# FT232H.net
KiCad netlist of a schematic drawn in EAGLE
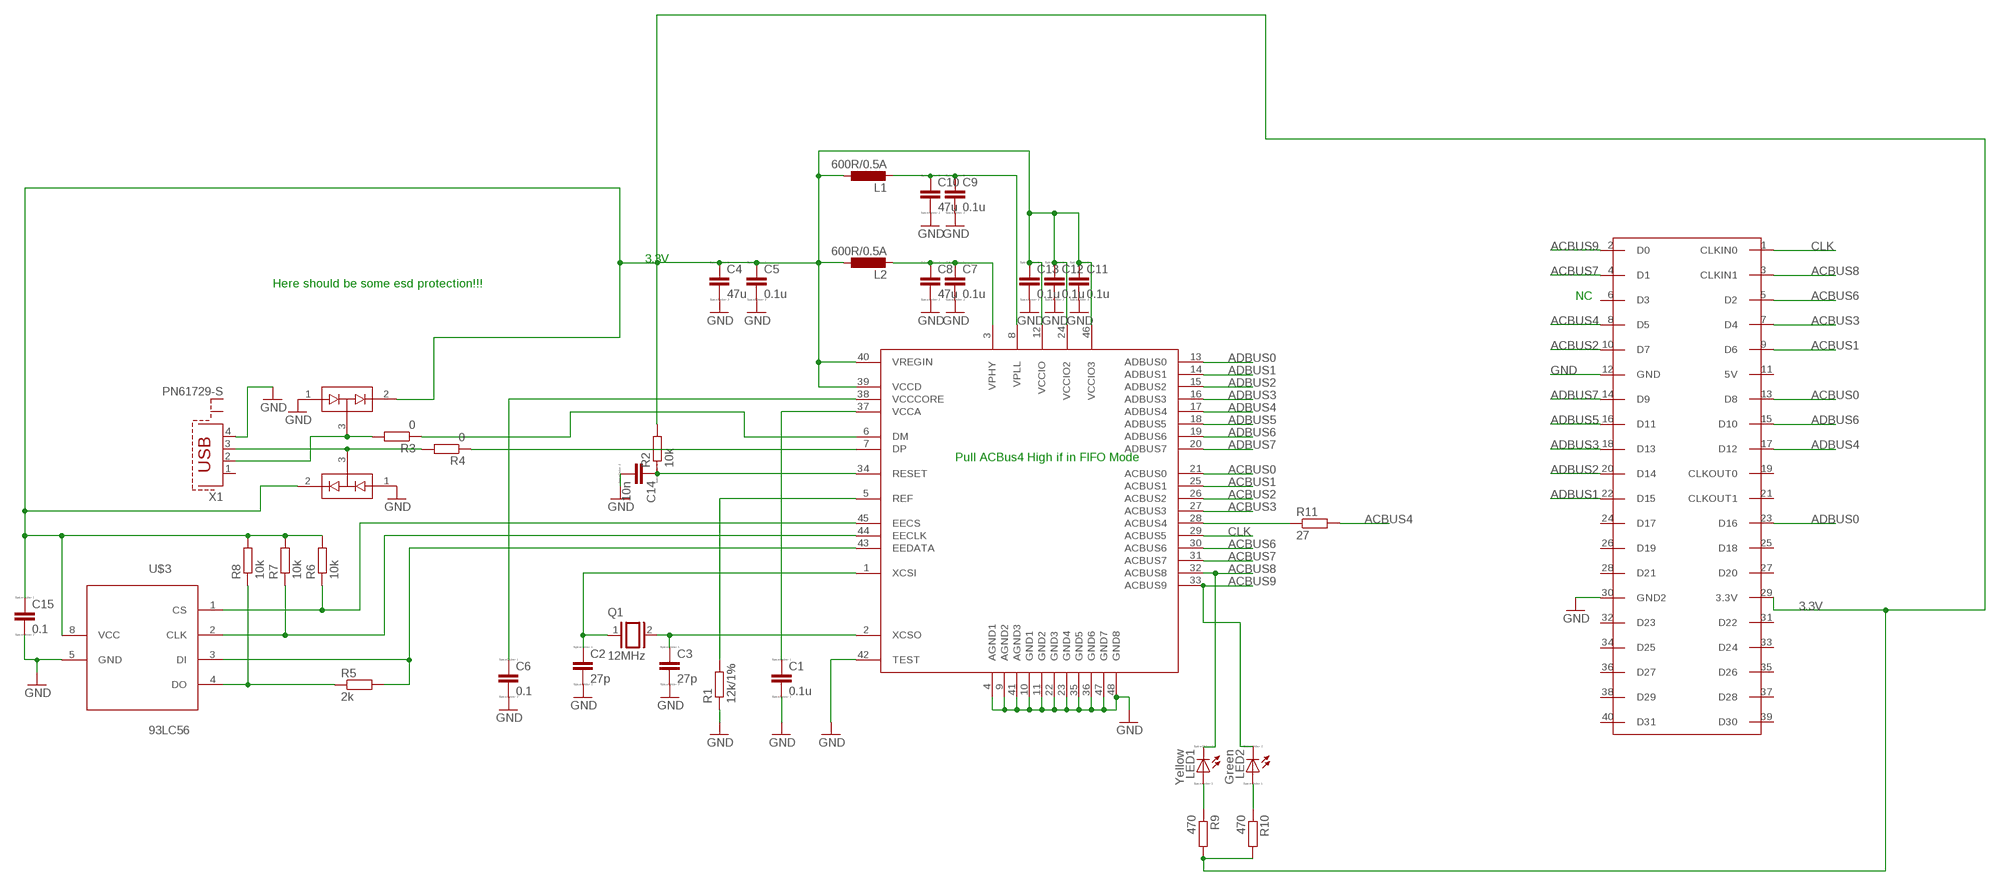
[diagram p0: schematic, sheet 1]

(export (version "E")
  (design (tool "Eeschema 10.0.6"))
  (components
    (comp (ref "C1")
      (value "0.1u")
      (footprint "eagle-import:C0805")
      (libsource (lib "eagle-import") (part "C_SMD"))
    )
    (comp (ref "C2")
      (value "27p")
      (footprint "eagle-import:C0805")
      (libsource (lib "eagle-import") (part "C_SMD"))
    )
    (comp (ref "C3")
      (value "27p")
      (footprint "eagle-import:C0805")
      (libsource (lib "eagle-import") (part "C_SMD"))
    )
    (comp (ref "C4")
      (value "47u")
      (footprint "eagle-import:C0805")
      (libsource (lib "eagle-import") (part "C_SMD"))
    )
    (comp (ref "C5")
      (value "0.1u")
      (footprint "eagle-import:C0805")
      (libsource (lib "eagle-import") (part "C_SMD"))
    )
    (comp (ref "C6")
      (value "0.1")
      (footprint "eagle-import:C0805")
      (libsource (lib "eagle-import") (part "C_SMD"))
    )
    (comp (ref "C7")
      (value "0.1u")
      (footprint "eagle-import:C0805")
      (libsource (lib "eagle-import") (part "C_SMD"))
    )
    (comp (ref "C8")
      (value "47u")
      (footprint "eagle-import:C0805")
      (libsource (lib "eagle-import") (part "C_SMD"))
    )
    (comp (ref "C9")
      (value "0.1u")
      (footprint "eagle-import:C0805")
      (libsource (lib "eagle-import") (part "C_SMD"))
    )
    (comp (ref "C10")
      (value "47u")
      (footprint "eagle-import:C0805")
      (libsource (lib "eagle-import") (part "C_SMD"))
    )
    (comp (ref "C11")
      (value "0.1u")
      (footprint "eagle-import:C0805")
      (libsource (lib "eagle-import") (part "C_SMD"))
    )
    (comp (ref "C12")
      (value "0.1u")
      (footprint "eagle-import:C0805")
      (libsource (lib "eagle-import") (part "C_SMD"))
    )
    (comp (ref "C13")
      (value "0.1u")
      (footprint "eagle-import:C0805")
      (libsource (lib "eagle-import") (part "C_SMD"))
    )
    (comp (ref "C14")
      (value "10n")
      (footprint "eagle-import:C0805")
      (libsource (lib "eagle-import") (part "C_SMD"))
    )
    (comp (ref "C15")
      (value "0.1")
      (footprint "eagle-import:C0805")
      (libsource (lib "eagle-import") (part "C_SMD"))
    )
    (comp (ref "D1")
      (value "BAV99")
      (footprint "eagle-import:SOT23")
      (libsource (lib "eagle-import") (part "BAV99"))
    )
    (comp (ref "D2")
      (value "BAV99")
      (footprint "eagle-import:SOT23")
      (libsource (lib "eagle-import") (part "BAV99"))
    )
    (comp (ref "L1")
      (value "600R/0.5A")
      (footprint "eagle-import:R0805")
      (libsource (lib "eagle-import") (part "L_0805"))
    )
    (comp (ref "L2")
      (value "600R/0.5A")
      (footprint "eagle-import:R0805")
      (libsource (lib "eagle-import") (part "L_0805"))
    )
    (comp (ref "LED1")
      (value "Yellow")
      (footprint "eagle-import:R0805")
      (libsource (lib "eagle-import") (part "LED_ELED_0805"))
    )
    (comp (ref "LED2")
      (value "Green")
      (footprint "eagle-import:R0805")
      (libsource (lib "eagle-import") (part "LED_ELED_0805"))
    )
    (comp (ref "Q1")
      (value "12MHz")
      (footprint "eagle-import:QS")
      (libsource (lib "eagle-import") (part "XTAL/S"))
    )
    (comp (ref "R1")
      (value "12k/1%")
      (footprint "eagle-import:M0805")
      (libsource (lib "eagle-import") (part "R-EU_M0805"))
    )
    (comp (ref "R2")
      (value "10k")
      (footprint "eagle-import:M0805")
      (libsource (lib "eagle-import") (part "R-EU_M0805"))
    )
    (comp (ref "R3")
      (value "0")
      (footprint "eagle-import:M0805")
      (libsource (lib "eagle-import") (part "R-EU_M0805"))
    )
    (comp (ref "R4")
      (value "0")
      (footprint "eagle-import:M0805")
      (libsource (lib "eagle-import") (part "R-EU_M0805"))
    )
    (comp (ref "R5")
      (value "2k")
      (footprint "eagle-import:M0805")
      (libsource (lib "eagle-import") (part "R-EU_M0805"))
    )
    (comp (ref "R6")
      (value "10k")
      (footprint "eagle-import:M0805")
      (libsource (lib "eagle-import") (part "R-EU_M0805"))
    )
    (comp (ref "R7")
      (value "10k")
      (footprint "eagle-import:M0805")
      (libsource (lib "eagle-import") (part "R-EU_M0805"))
    )
    (comp (ref "R8")
      (value "10k")
      (footprint "eagle-import:M0805")
      (libsource (lib "eagle-import") (part "R-EU_M0805"))
    )
    (comp (ref "R9")
      (value "470")
      (footprint "eagle-import:M0805")
      (libsource (lib "eagle-import") (part "R-EU_M0805"))
    )
    (comp (ref "R10")
      (value "470")
      (footprint "eagle-import:M0805")
      (libsource (lib "eagle-import") (part "R-EU_M0805"))
    )
    (comp (ref "R11")
      (value "27")
      (footprint "eagle-import:M0805")
      (libsource (lib "eagle-import") (part "R-EU_M0805"))
    )
    (comp (ref "U$1")
      (value "FT232H")
      (footprint "eagle-import:LQFP48")
      (libsource (lib "eagle-import") (part "FT232H"))
    )
    (comp (ref "U$2")
      (value "FPGA_GPIO_DE0")
      (footprint "eagle-import:2X20")
      (libsource (lib "eagle-import") (part "FPGA_GPIO_DE0"))
    )
    (comp (ref "U$3")
      (value "93LC56")
      (footprint "eagle-import:DIL-08")
      (libsource (lib "eagle-import") (part "93LC56"))
    )
    (comp (ref "X1")
      (value "PN61729-S")
      (footprint "eagle-import:PN61729-S")
      (libsource (lib "eagle-import") (part "PN61729-S"))
    )
  )
  (nets
    (net (code "1") (name "/3.3V") (class "Default")
      (node (ref "C11") (pin "1") (pinfunction "1_1") (pintype "passive"))
      (node (ref "C12") (pin "1") (pinfunction "1_1") (pintype "passive"))
      (node (ref "C13") (pin "1") (pinfunction "1_1") (pintype "passive"))
      (node (ref "C15") (pin "1") (pinfunction "1_1") (pintype "passive"))
      (node (ref "C4") (pin "1") (pinfunction "1_1") (pintype "passive"))
      (node (ref "C5") (pin "1") (pinfunction "1_1") (pintype "passive"))
      (node (ref "D1") (pin "2") (pinfunction "C2_2") (pintype "bidirectional"))
      (node (ref "D2") (pin "2") (pinfunction "C2_2") (pintype "bidirectional"))
      (node (ref "L1") (pin "1") (pinfunction "1_1") (pintype "passive"))
      (node (ref "L2") (pin "1") (pinfunction "1_1") (pintype "passive"))
      (node (ref "R10") (pin "2") (pinfunction "2_2") (pintype "passive"))
      (node (ref "R2") (pin "2") (pinfunction "2_2") (pintype "passive"))
      (node (ref "R6") (pin "2") (pinfunction "2_2") (pintype "passive"))
      (node (ref "R7") (pin "2") (pinfunction "2_2") (pintype "passive"))
      (node (ref "R8") (pin "2") (pinfunction "2_2") (pintype "passive"))
      (node (ref "R9") (pin "2") (pinfunction "2_2") (pintype "passive"))
      (node (ref "U$1") (pin "12") (pinfunction "VCCIO_12") (pintype "bidirectional"))
      (node (ref "U$1") (pin "24") (pinfunction "VCCIO2_24") (pintype "bidirectional"))
      (node (ref "U$1") (pin "39") (pinfunction "VCCD_39") (pintype "bidirectional"))
      (node (ref "U$1") (pin "40") (pinfunction "VREGIN_40") (pintype "bidirectional"))
      (node (ref "U$1") (pin "46") (pinfunction "VCCIO3_46") (pintype "bidirectional"))
      (node (ref "U$2") (pin "29") (pinfunction "3.3V_29") (pintype "bidirectional"))
      (node (ref "U$3") (pin "8") (pinfunction "VCC_8") (pintype "bidirectional"))
    )
    (net (code "2") (name "/ACBUS0") (class "Default")
      (node (ref "U$1") (pin "21") (pinfunction "ACBUS0_21") (pintype "bidirectional"))
      (node (ref "U$2") (pin "13") (pinfunction "D8_13") (pintype "bidirectional"))
    )
    (net (code "3") (name "/ACBUS1") (class "Default")
      (node (ref "U$1") (pin "25") (pinfunction "ACBUS1_25") (pintype "bidirectional"))
      (node (ref "U$2") (pin "9") (pinfunction "D6_9") (pintype "bidirectional"))
    )
    (net (code "4") (name "/ACBUS2") (class "Default")
      (node (ref "U$1") (pin "26") (pinfunction "ACBUS2_26") (pintype "bidirectional"))
      (node (ref "U$2") (pin "10") (pinfunction "D7_10") (pintype "bidirectional"))
    )
    (net (code "5") (name "/ACBUS3") (class "Default")
      (node (ref "U$1") (pin "27") (pinfunction "ACBUS3_27") (pintype "bidirectional"))
      (node (ref "U$2") (pin "7") (pinfunction "D4_7") (pintype "bidirectional"))
    )
    (net (code "6") (name "/ACBUS4") (class "Default")
      (node (ref "R11") (pin "2") (pinfunction "2_2") (pintype "passive"))
      (node (ref "U$2") (pin "8") (pinfunction "D5_8") (pintype "bidirectional"))
    )
    (net (code "7") (name "/ACBUS6") (class "Default")
      (node (ref "U$1") (pin "30") (pinfunction "ACBUS6_30") (pintype "bidirectional"))
      (node (ref "U$2") (pin "5") (pinfunction "D2_5") (pintype "bidirectional"))
    )
    (net (code "8") (name "/ACBUS7") (class "Default")
      (node (ref "U$1") (pin "31") (pinfunction "ACBUS7_31") (pintype "bidirectional"))
      (node (ref "U$2") (pin "4") (pinfunction "D1_4") (pintype "bidirectional"))
    )
    (net (code "9") (name "/ACBUS8") (class "Default")
      (node (ref "LED1") (pin "2") (pinfunction "C_2") (pintype "passive"))
      (node (ref "U$1") (pin "32") (pinfunction "ACBUS8_32") (pintype "bidirectional"))
      (node (ref "U$2") (pin "3") (pinfunction "CLKIN1_3") (pintype "bidirectional"))
    )
    (net (code "10") (name "/ACBUS9") (class "Default")
      (node (ref "LED2") (pin "2") (pinfunction "C_2") (pintype "passive"))
      (node (ref "U$1") (pin "33") (pinfunction "ACBUS9_33") (pintype "bidirectional"))
      (node (ref "U$2") (pin "2") (pinfunction "D0_2") (pintype "bidirectional"))
    )
    (net (code "11") (name "/ADBUS0") (class "Default")
      (node (ref "U$1") (pin "13") (pinfunction "ADBUS0_13") (pintype "bidirectional"))
      (node (ref "U$2") (pin "23") (pinfunction "D16_23") (pintype "bidirectional"))
    )
    (net (code "12") (name "/ADBUS1") (class "Default")
      (node (ref "U$1") (pin "14") (pinfunction "ADBUS1_14") (pintype "bidirectional"))
      (node (ref "U$2") (pin "22") (pinfunction "D15_22") (pintype "bidirectional"))
    )
    (net (code "13") (name "/ADBUS2") (class "Default")
      (node (ref "U$1") (pin "15") (pinfunction "ADBUS2_15") (pintype "bidirectional"))
      (node (ref "U$2") (pin "20") (pinfunction "D14_20") (pintype "bidirectional"))
    )
    (net (code "14") (name "/ADBUS3") (class "Default")
      (node (ref "U$1") (pin "16") (pinfunction "ADBUS3_16") (pintype "bidirectional"))
      (node (ref "U$2") (pin "18") (pinfunction "D13_18") (pintype "bidirectional"))
    )
    (net (code "15") (name "/ADBUS4") (class "Default")
      (node (ref "U$1") (pin "17") (pinfunction "ADBUS4_17") (pintype "bidirectional"))
      (node (ref "U$2") (pin "17") (pinfunction "D12_17") (pintype "bidirectional"))
    )
    (net (code "16") (name "/ADBUS5") (class "Default")
      (node (ref "U$1") (pin "18") (pinfunction "ADBUS5_18") (pintype "bidirectional"))
      (node (ref "U$2") (pin "16") (pinfunction "D11_16") (pintype "bidirectional"))
    )
    (net (code "17") (name "/ADBUS6") (class "Default")
      (node (ref "U$1") (pin "19") (pinfunction "ADBUS6_19") (pintype "bidirectional"))
      (node (ref "U$2") (pin "15") (pinfunction "D10_15") (pintype "bidirectional"))
    )
    (net (code "18") (name "/ADBUS7") (class "Default")
      (node (ref "U$1") (pin "20") (pinfunction "ADBUS7_20") (pintype "bidirectional"))
      (node (ref "U$2") (pin "14") (pinfunction "D9_14") (pintype "bidirectional"))
    )
    (net (code "19") (name "/CLK") (class "Default")
      (node (ref "U$1") (pin "29") (pinfunction "ACBUS5_29") (pintype "bidirectional"))
      (node (ref "U$2") (pin "1") (pinfunction "CLKIN0_1") (pintype "bidirectional"))
    )
    (net (code "20") (name "GND") (class "Default")
      (node (ref "C1") (pin "2") (pinfunction "2_2") (pintype "passive"))
      (node (ref "C10") (pin "2") (pinfunction "2_2") (pintype "passive"))
      (node (ref "C11") (pin "2") (pinfunction "2_2") (pintype "passive"))
      (node (ref "C12") (pin "2") (pinfunction "2_2") (pintype "passive"))
      (node (ref "C13") (pin "2") (pinfunction "2_2") (pintype "passive"))
      (node (ref "C14") (pin "2") (pinfunction "2_2") (pintype "passive"))
      (node (ref "C15") (pin "2") (pinfunction "2_2") (pintype "passive"))
      (node (ref "C2") (pin "2") (pinfunction "2_2") (pintype "passive"))
      (node (ref "C3") (pin "2") (pinfunction "2_2") (pintype "passive"))
      (node (ref "C4") (pin "2") (pinfunction "2_2") (pintype "passive"))
      (node (ref "C5") (pin "2") (pinfunction "2_2") (pintype "passive"))
      (node (ref "C6") (pin "2") (pinfunction "2_2") (pintype "passive"))
      (node (ref "C7") (pin "2") (pinfunction "2_2") (pintype "passive"))
      (node (ref "C8") (pin "2") (pinfunction "2_2") (pintype "passive"))
      (node (ref "C9") (pin "2") (pinfunction "2_2") (pintype "passive"))
      (node (ref "D1") (pin "1") (pinfunction "A1_1") (pintype "bidirectional"))
      (node (ref "D2") (pin "1") (pinfunction "A1_1") (pintype "bidirectional"))
      (node (ref "R1") (pin "1") (pinfunction "1_1") (pintype "passive"))
      (node (ref "U$1") (pin "10") (pinfunction "GND1_10") (pintype "bidirectional"))
      (node (ref "U$1") (pin "11") (pinfunction "GND2_11") (pintype "bidirectional"))
      (node (ref "U$1") (pin "22") (pinfunction "GND3_22") (pintype "bidirectional"))
      (node (ref "U$1") (pin "23") (pinfunction "GND4_23") (pintype "bidirectional"))
      (node (ref "U$1") (pin "35") (pinfunction "GND5_35") (pintype "bidirectional"))
      (node (ref "U$1") (pin "36") (pinfunction "GND6_36") (pintype "bidirectional"))
      (node (ref "U$1") (pin "4") (pinfunction "AGND1_4") (pintype "bidirectional"))
      (node (ref "U$1") (pin "41") (pinfunction "AGND3_41") (pintype "bidirectional"))
      (node (ref "U$1") (pin "42") (pinfunction "TEST_42") (pintype "bidirectional"))
      (node (ref "U$1") (pin "47") (pinfunction "GND7_47") (pintype "bidirectional"))
      (node (ref "U$1") (pin "48") (pinfunction "GND8_48") (pintype "bidirectional"))
      (node (ref "U$1") (pin "9") (pinfunction "AGND2_9") (pintype "bidirectional"))
      (node (ref "U$2") (pin "12") (pinfunction "GND_12") (pintype "bidirectional"))
      (node (ref "U$2") (pin "30") (pinfunction "GND2_30") (pintype "bidirectional"))
      (node (ref "U$3") (pin "5") (pinfunction "GND_5") (pintype "bidirectional"))
      (node (ref "X1") (pin "4") (pinfunction "4_4") (pintype "passive"))
    )
    (net (code "21") (name "Net-(D1-COM)") (class "Default")
      (node (ref "D1") (pin "3") (pinfunction "COM_3") (pintype "bidirectional"))
      (node (ref "R3") (pin "2") (pinfunction "2_2") (pintype "passive"))
      (node (ref "X1") (pin "2") (pinfunction "2_2") (pintype "passive"))
    )
    (net (code "22") (name "Net-(D2-COM)") (class "Default")
      (node (ref "D2") (pin "3") (pinfunction "COM_3") (pintype "bidirectional"))
      (node (ref "R4") (pin "2") (pinfunction "2_2") (pintype "passive"))
      (node (ref "X1") (pin "3") (pinfunction "3_3") (pintype "passive"))
    )
    (net (code "23") (name "Net-(LED1-A)") (class "Default")
      (node (ref "LED1") (pin "1") (pinfunction "A_1") (pintype "passive"))
      (node (ref "R9") (pin "1") (pinfunction "1_1") (pintype "passive"))
    )
    (net (code "24") (name "Net-(LED2-A)") (class "Default")
      (node (ref "LED2") (pin "1") (pinfunction "A_1") (pintype "passive"))
      (node (ref "R10") (pin "1") (pinfunction "1_1") (pintype "passive"))
    )
    (net (code "25") (name "Net-(U$1-ACBUS4)") (class "Default")
      (node (ref "R11") (pin "1") (pinfunction "1_1") (pintype "passive"))
      (node (ref "U$1") (pin "28") (pinfunction "ACBUS4_28") (pintype "bidirectional"))
    )
    (net (code "26") (name "Net-(U$1-DM)") (class "Default")
      (node (ref "R3") (pin "1") (pinfunction "1_1") (pintype "passive"))
      (node (ref "U$1") (pin "6") (pinfunction "DM_6") (pintype "bidirectional"))
    )
    (net (code "27") (name "Net-(U$1-DP)") (class "Default")
      (node (ref "R4") (pin "1") (pinfunction "1_1") (pintype "passive"))
      (node (ref "U$1") (pin "7") (pinfunction "DP_7") (pintype "bidirectional"))
    )
    (net (code "28") (name "Net-(U$1-EECLK)") (class "Default")
      (node (ref "R7") (pin "1") (pinfunction "1_1") (pintype "passive"))
      (node (ref "U$1") (pin "44") (pinfunction "EECLK_44") (pintype "bidirectional"))
      (node (ref "U$3") (pin "2") (pinfunction "CLK_2") (pintype "bidirectional"))
    )
    (net (code "29") (name "Net-(U$1-EECS)") (class "Default")
      (node (ref "R6") (pin "1") (pinfunction "1_1") (pintype "passive"))
      (node (ref "U$1") (pin "45") (pinfunction "EECS_45") (pintype "bidirectional"))
      (node (ref "U$3") (pin "1") (pinfunction "CS_1") (pintype "bidirectional"))
    )
    (net (code "30") (name "Net-(U$1-EEDATA)") (class "Default")
      (node (ref "R5") (pin "2") (pinfunction "2_2") (pintype "passive"))
      (node (ref "U$1") (pin "43") (pinfunction "EEDATA_43") (pintype "bidirectional"))
      (node (ref "U$3") (pin "3") (pinfunction "DI_3") (pintype "bidirectional"))
    )
    (net (code "31") (name "Net-(U$1-REF)") (class "Default")
      (node (ref "R1") (pin "2") (pinfunction "2_2") (pintype "passive"))
      (node (ref "U$1") (pin "5") (pinfunction "REF_5") (pintype "bidirectional"))
    )
    (net (code "32") (name "Net-(U$1-RESET)") (class "Default")
      (node (ref "C14") (pin "1") (pinfunction "1_1") (pintype "passive"))
      (node (ref "R2") (pin "1") (pinfunction "1_1") (pintype "passive"))
      (node (ref "U$1") (pin "34") (pinfunction "RESET_34") (pintype "bidirectional"))
    )
    (net (code "33") (name "Net-(U$1-VCCA)") (class "Default")
      (node (ref "C1") (pin "1") (pinfunction "1_1") (pintype "passive"))
      (node (ref "U$1") (pin "37") (pinfunction "VCCA_37") (pintype "bidirectional"))
    )
    (net (code "34") (name "Net-(U$1-VCCCORE)") (class "Default")
      (node (ref "C6") (pin "1") (pinfunction "1_1") (pintype "passive"))
      (node (ref "U$1") (pin "38") (pinfunction "VCCCORE_38") (pintype "bidirectional"))
    )
    (net (code "35") (name "Net-(U$1-VPHY)") (class "Default")
      (node (ref "C7") (pin "1") (pinfunction "1_1") (pintype "passive"))
      (node (ref "C8") (pin "1") (pinfunction "1_1") (pintype "passive"))
      (node (ref "L2") (pin "2") (pinfunction "2_2") (pintype "passive"))
      (node (ref "U$1") (pin "3") (pinfunction "VPHY_3") (pintype "bidirectional"))
    )
    (net (code "36") (name "Net-(U$1-VPLL)") (class "Default")
      (node (ref "C10") (pin "1") (pinfunction "1_1") (pintype "passive"))
      (node (ref "C9") (pin "1") (pinfunction "1_1") (pintype "passive"))
      (node (ref "L1") (pin "2") (pinfunction "2_2") (pintype "passive"))
      (node (ref "U$1") (pin "8") (pinfunction "VPLL_8") (pintype "bidirectional"))
    )
    (net (code "37") (name "Net-(U$1-XCSI)") (class "Default")
      (node (ref "C2") (pin "1") (pinfunction "1_1") (pintype "passive"))
      (node (ref "Q1") (pin "1") (pinfunction "1_1") (pintype "passive"))
      (node (ref "U$1") (pin "1") (pinfunction "XCSI_1") (pintype "bidirectional"))
    )
    (net (code "38") (name "Net-(U$1-XCSO)") (class "Default")
      (node (ref "C3") (pin "1") (pinfunction "1_1") (pintype "passive"))
      (node (ref "Q1") (pin "2") (pinfunction "2_2") (pintype "passive"))
      (node (ref "U$1") (pin "2") (pinfunction "XCSO_2") (pintype "bidirectional"))
    )
    (net (code "39") (name "Net-(U$3-DO)") (class "Default")
      (node (ref "R5") (pin "1") (pinfunction "1_1") (pintype "passive"))
      (node (ref "R8") (pin "1") (pinfunction "1_1") (pintype "passive"))
      (node (ref "U$3") (pin "4") (pinfunction "DO_4") (pintype "bidirectional"))
    )
    (net (code "40") (name "unconnected-(U$2-5V-Pad11)") (class "Default")
      (node (ref "U$2") (pin "11") (pinfunction "5V_11") (pintype "bidirectional"))
    )
    (net (code "41") (name "unconnected-(U$2-CLKOUT0-Pad19)") (class "Default")
      (node (ref "U$2") (pin "19") (pinfunction "CLKOUT0_19") (pintype "bidirectional"))
    )
    (net (code "42") (name "unconnected-(U$2-CLKOUT1-Pad21)") (class "Default")
      (node (ref "U$2") (pin "21") (pinfunction "CLKOUT1_21") (pintype "bidirectional"))
    )
    (net (code "43") (name "unconnected-(U$2-D3-Pad6)") (class "Default")
      (node (ref "U$2") (pin "6") (pinfunction "D3_6") (pintype "bidirectional"))
    )
    (net (code "44") (name "unconnected-(U$2-D17-Pad24)") (class "Default")
      (node (ref "U$2") (pin "24") (pinfunction "D17_24") (pintype "bidirectional"))
    )
    (net (code "45") (name "unconnected-(U$2-D18-Pad25)") (class "Default")
      (node (ref "U$2") (pin "25") (pinfunction "D18_25") (pintype "bidirectional"))
    )
    (net (code "46") (name "unconnected-(U$2-D19-Pad26)") (class "Default")
      (node (ref "U$2") (pin "26") (pinfunction "D19_26") (pintype "bidirectional"))
    )
    (net (code "47") (name "unconnected-(U$2-D20-Pad27)") (class "Default")
      (node (ref "U$2") (pin "27") (pinfunction "D20_27") (pintype "bidirectional"))
    )
    (net (code "48") (name "unconnected-(U$2-D21-Pad28)") (class "Default")
      (node (ref "U$2") (pin "28") (pinfunction "D21_28") (pintype "bidirectional"))
    )
    (net (code "49") (name "unconnected-(U$2-D22-Pad31)") (class "Default")
      (node (ref "U$2") (pin "31") (pinfunction "D22_31") (pintype "bidirectional"))
    )
    (net (code "50") (name "unconnected-(U$2-D23-Pad32)") (class "Default")
      (node (ref "U$2") (pin "32") (pinfunction "D23_32") (pintype "bidirectional"))
    )
    (net (code "51") (name "unconnected-(U$2-D24-Pad33)") (class "Default")
      (node (ref "U$2") (pin "33") (pinfunction "D24_33") (pintype "bidirectional"))
    )
    (net (code "52") (name "unconnected-(U$2-D25-Pad34)") (class "Default")
      (node (ref "U$2") (pin "34") (pinfunction "D25_34") (pintype "bidirectional"))
    )
    (net (code "53") (name "unconnected-(U$2-D26-Pad35)") (class "Default")
      (node (ref "U$2") (pin "35") (pinfunction "D26_35") (pintype "bidirectional"))
    )
    (net (code "54") (name "unconnected-(U$2-D27-Pad36)") (class "Default")
      (node (ref "U$2") (pin "36") (pinfunction "D27_36") (pintype "bidirectional"))
    )
    (net (code "55") (name "unconnected-(U$2-D28-Pad37)") (class "Default")
      (node (ref "U$2") (pin "37") (pinfunction "D28_37") (pintype "bidirectional"))
    )
    (net (code "56") (name "unconnected-(U$2-D29-Pad38)") (class "Default")
      (node (ref "U$2") (pin "38") (pinfunction "D29_38") (pintype "bidirectional"))
    )
    (net (code "57") (name "unconnected-(U$2-D30-Pad39)") (class "Default")
      (node (ref "U$2") (pin "39") (pinfunction "D30_39") (pintype "bidirectional"))
    )
    (net (code "58") (name "unconnected-(U$2-D31-Pad40)") (class "Default")
      (node (ref "U$2") (pin "40") (pinfunction "D31_40") (pintype "bidirectional"))
    )
    (net (code "59") (name "unconnected-(X1-Pad1)") (class "Default")
      (node (ref "X1") (pin "1") (pinfunction "1_1") (pintype "passive"))
    )
    (net (code "60") (name "unconnected-(X1-PadS1)") (class "Default")
      (node (ref "X1") (pin "S1") (pinfunction "S1_S1") (pintype "passive"))
    )
    (net (code "61") (name "unconnected-(X1-PadS2)") (class "Default")
      (node (ref "X1") (pin "S2") (pinfunction "S2_S2") (pintype "passive"))
    )
  )
)
